# DIGISPARK_PRODUCTION_REV3.net
KiCad netlist of a schematic drawn in EAGLE
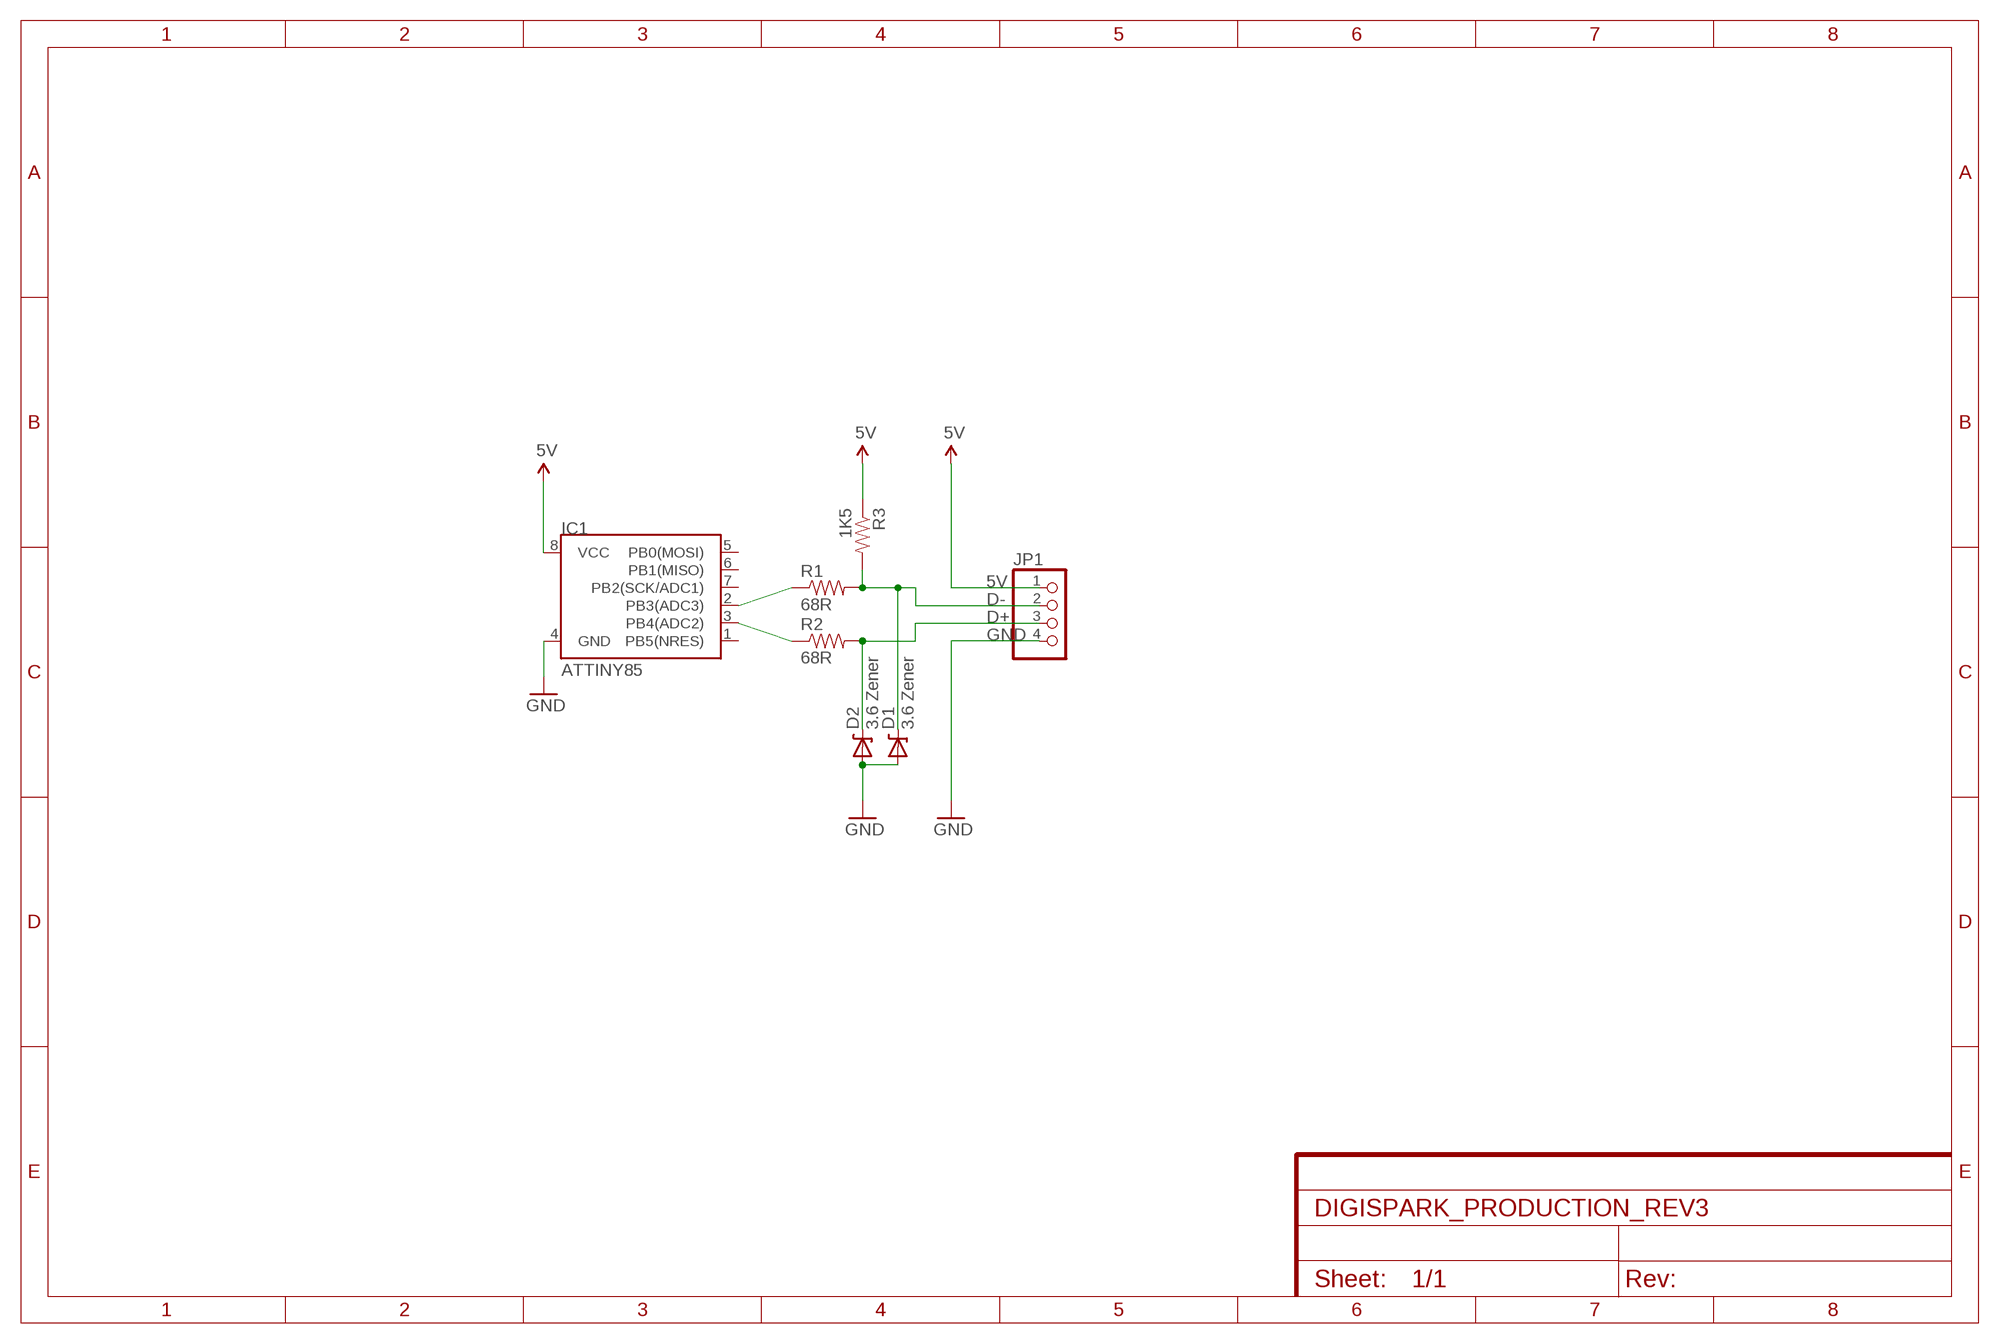
[diagram p0: schematic, sheet 1]

(export (version "E")
  (design (tool "Eeschema 10.0.6"))
  (components
    (comp (ref "D1")
      (value "3.6 Zener")
      (footprint "eagle-import:SOD-323")
      (libsource (lib "eagle-import") (part "DIODE-ZENER-BZT52"))
    )
    (comp (ref "D2")
      (value "3.6 Zener")
      (footprint "eagle-import:SOD-323")
      (libsource (lib "eagle-import") (part "DIODE-ZENER-BZT52"))
    )
    (comp (ref "IC1")
      (value "ATTINY85")
      (footprint "eagle-import:SO08-EIAJ")
      (libsource (lib "eagle-import") (part "ATTINY45"))
    )
    (comp (ref "JP1")
      (value "PINHD-1X4")
      (footprint "eagle-import:1X04")
      (libsource (lib "eagle-import") (part "PINHD-1X4"))
    )
    (comp (ref "R1")
      (value "68R")
      (footprint "eagle-import:0402-RES")
      (libsource (lib "eagle-import") (part "RESISTOR0402-RES"))
    )
    (comp (ref "R2")
      (value "68R")
      (footprint "eagle-import:0402-RES")
      (libsource (lib "eagle-import") (part "RESISTOR0402-RES"))
    )
    (comp (ref "R3")
      (value "1K5")
      (footprint "eagle-import:0402-RES")
      (libsource (lib "eagle-import") (part "RESISTOR0402-RES"))
    )
  )
  (nets
    (net (code "1") (name "/D+") (class "Default")
      (node (ref "D2") (pin "1") (pinfunction "C_1") (pintype "passive"))
      (node (ref "JP1") (pin "3") (pinfunction "3_3") (pintype "passive"))
      (node (ref "R2") (pin "2") (pinfunction "2_2") (pintype "passive"))
    )
    (net (code "2") (name "/D-") (class "Default")
      (node (ref "D1") (pin "1") (pinfunction "C_1") (pintype "passive"))
      (node (ref "JP1") (pin "2") (pinfunction "2_2") (pintype "passive"))
      (node (ref "R1") (pin "2") (pinfunction "2_2") (pintype "passive"))
      (node (ref "R3") (pin "2") (pinfunction "2_2") (pintype "passive"))
    )
    (net (code "3") (name "5V") (class "Default")
      (node (ref "IC1") (pin "8") (pinfunction "VCC_8") (pintype "bidirectional"))
      (node (ref "JP1") (pin "1") (pinfunction "1_1") (pintype "passive"))
      (node (ref "R3") (pin "1") (pinfunction "1_1") (pintype "passive"))
    )
    (net (code "4") (name "GND") (class "Default")
      (node (ref "D1") (pin "2") (pinfunction "A_2") (pintype "passive"))
      (node (ref "D2") (pin "2") (pinfunction "A_2") (pintype "passive"))
      (node (ref "IC1") (pin "4") (pinfunction "GND_4") (pintype "bidirectional"))
      (node (ref "JP1") (pin "4") (pinfunction "4_4") (pintype "passive"))
    )
    (net (code "5") (name "Net-(IC1-PB3(ADC3))") (class "Default")
      (node (ref "IC1") (pin "2") (pinfunction "PB3(ADC3)_2") (pintype "bidirectional"))
      (node (ref "R1") (pin "1") (pinfunction "1_1") (pintype "passive"))
    )
    (net (code "6") (name "Net-(IC1-PB4(ADC2))") (class "Default")
      (node (ref "IC1") (pin "3") (pinfunction "PB4(ADC2)_3") (pintype "bidirectional"))
      (node (ref "R2") (pin "1") (pinfunction "1_1") (pintype "passive"))
    )
    (net (code "7") (name "unconnected-(IC1-PB0(MOSI)-Pad5)") (class "Default")
      (node (ref "IC1") (pin "5") (pinfunction "PB0(MOSI)_5") (pintype "bidirectional"))
    )
    (net (code "8") (name "unconnected-(IC1-PB1(MISO)-Pad6)") (class "Default")
      (node (ref "IC1") (pin "6") (pinfunction "PB1(MISO)_6") (pintype "bidirectional"))
    )
    (net (code "9") (name "unconnected-(IC1-PB2(SCK{slash}ADC1)-Pad7)") (class "Default")
      (node (ref "IC1") (pin "7") (pinfunction "PB2(SCK/ADC1)_7") (pintype "bidirectional"))
    )
    (net (code "10") (name "unconnected-(IC1-PB5(NRES)-Pad1)") (class "Default")
      (node (ref "IC1") (pin "1") (pinfunction "PB5(NRES)_1") (pintype "bidirectional"))
    )
  )
)
